# radio.net
KiCad netlist of a schematic drawn in Altium Designer
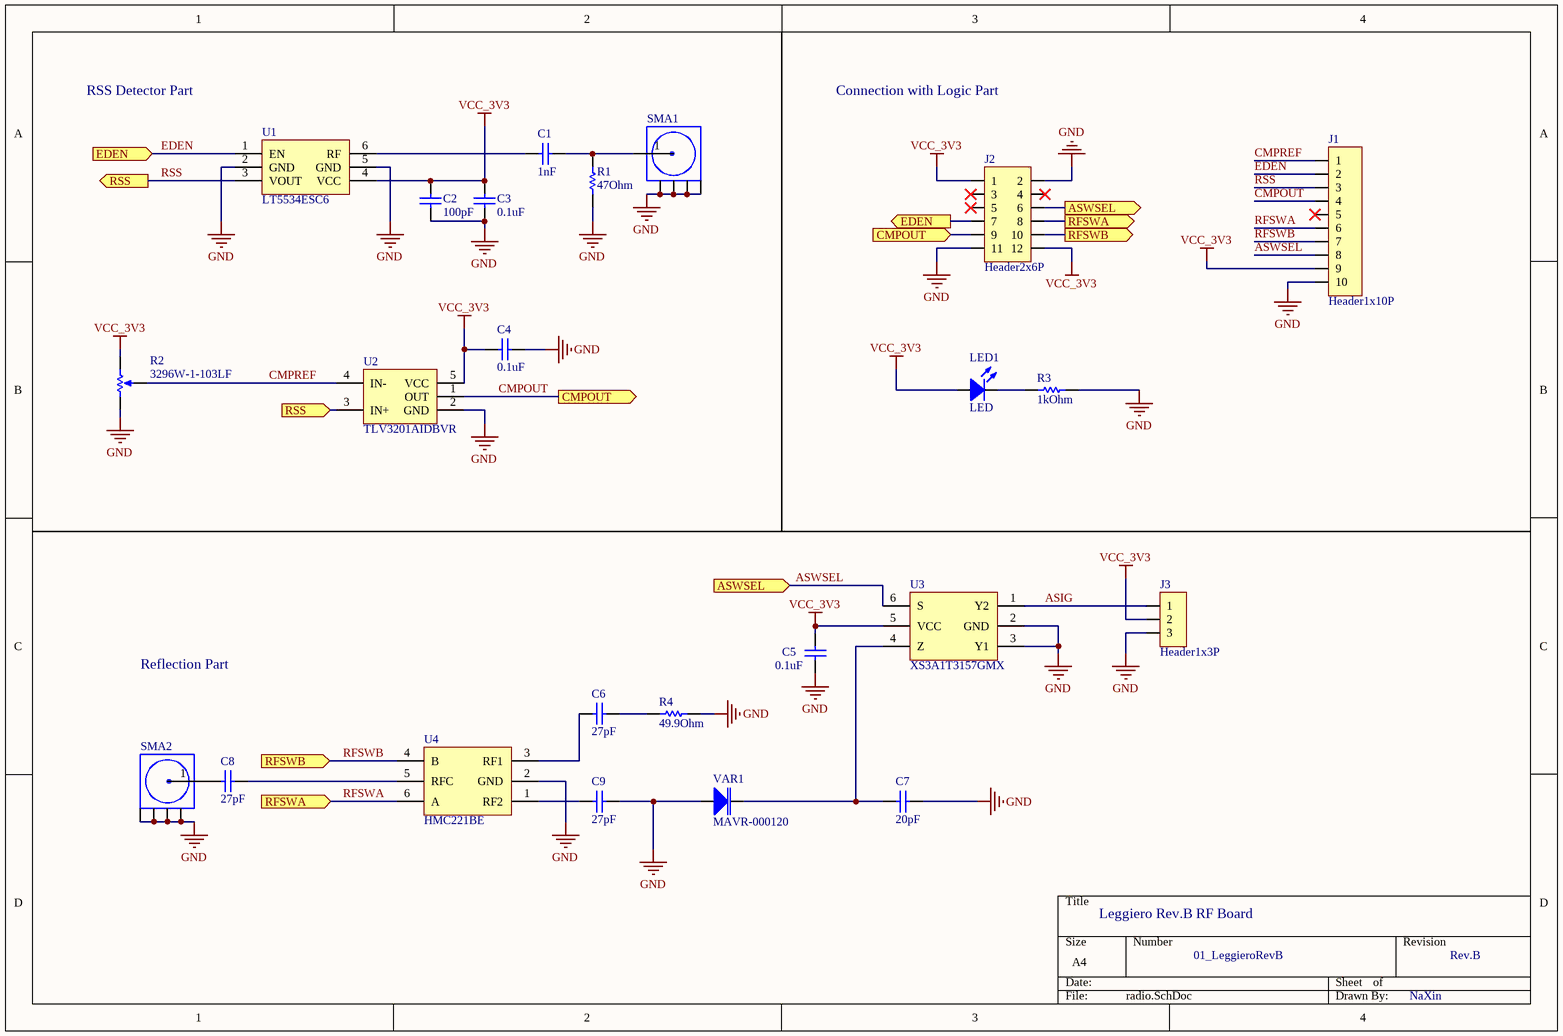
[diagram p0: radio.SchDoc]

(export (version "E")
  (design (tool "Eeschema 10.0.6"))
  (components
    (comp (ref "C1")
      (value "1nF")
      (footprint "C0402")
      (description "C597016")
      (libsource (lib "leggiero") (part "Cap"))
    )
    (comp (ref "C2") (value "100pF") (footprint "C0603") (libsource (lib "leggiero") (part "Cap")))
    (comp (ref "C3") (value "0.1uF") (footprint "C0402") (libsource (lib "leggiero") (part "Cap")))
    (comp (ref "C4") (value "0.1uF") (footprint "C0402") (libsource (lib "leggiero") (part "Cap")))
    (comp (ref "C5") (value "0.1uF") (footprint "C0402") (libsource (lib "leggiero") (part "Cap")))
    (comp (ref "C6")
      (value "27pF")
      (footprint "C0402")
      (description "C88883")
      (libsource (lib "leggiero") (part "Cap"))
    )
    (comp (ref "C7") (value "20pF") (footprint "C0402") (libsource (lib "leggiero") (part "Cap")))
    (comp (ref "C8")
      (value "27pF")
      (footprint "C0402")
      (description "C88883")
      (libsource (lib "leggiero") (part "Cap"))
    )
    (comp (ref "C9")
      (value "27pF")
      (footprint "C0402")
      (description "C88883")
      (libsource (lib "leggiero") (part "Cap"))
    )
    (comp (ref "J1")
      (value "Header1x10P")
      (footprint "Header1x10P")
      (description "C5156617")
      (libsource (lib "leggiero") (part "Header1x10P"))
    )
    (comp (ref "J2")
      (value "Header2x6P")
      (footprint "Header2x6P")
      (description "C92269")
      (libsource (lib "leggiero") (part "Header2x6P"))
    )
    (comp (ref "J3")
      (value "Header1x3P")
      (footprint "Header1x3P")
      (description "C7430359")
      (libsource (lib "leggiero") (part "Header1x3P"))
    )
    (comp (ref "LED1") (value "LED") (footprint "LED0603") (libsource (lib "leggiero") (part "LED")))
    (comp (ref "R1")
      (value "47Ohm")
      (footprint "R0402")
      (description "C491103")
      (libsource (lib "leggiero") (part "Res"))
    )
    (comp (ref "R2")
      (value "3296W-1-103LF")
      (footprint "3296W-1-103LF")
      (description "C34846")
      (libsource (lib "leggiero") (part "3296W-1-103LF"))
    )
    (comp (ref "R3") (value "1kOhm") (footprint "R0402") (libsource (lib "leggiero") (part "Res")))
    (comp (ref "R4")
      (value "49.9Ohm")
      (footprint "R0402")
      (description "C851030")
      (libsource (lib "leggiero") (part "Res"))
    )
    (comp (ref "SMA1")
      (value "RF2203017")
      (footprint "RF2203017")
      (description "C2982575")
      (libsource (lib "") (part "RF2203017_1"))
    )
    (comp (ref "SMA2")
      (value "RF2203017")
      (footprint "RF2203017")
      (description "C2982575")
      (libsource (lib "leggiero") (part "RF2203017"))
    )
    (comp (ref "U1")
      (value "LT5534ESC6")
      (footprint "LT5534ESC6#TRPBF")
      (description "C459867")
      (libsource (lib "leggiero") (part "LT5534ESC6"))
    )
    (comp (ref "U2")
      (value "TLV3201AIDBVR")
      (footprint "TLV3201AIDBVR")
      (description "C105188")
      (libsource (lib "leggiero") (part "TLV3201AIDBVR"))
    )
    (comp (ref "U3")
      (value "XS3A1T3157GMX")
      (footprint "XSON6_115")
      (description "C3657276")
      (libsource (lib "leggiero") (part "XS3A1T3157GMX"))
    )
    (comp (ref "U4")
      (value "HMC221BE")
      (footprint "SOT-23-6")
      (description "C1526247")
      (libsource (lib "leggiero") (part "HMC221BE"))
    )
    (comp (ref "VAR1")
      (value "MAVR-000120")
      (footprint "D0201")
      (description "C5139746")
      (libsource (lib "leggiero") (part "MAVR-000120"))
    )
  )
  (nets
    (net (code "1") (name "/ASIG") (class "Default")
      (node (ref "J3") (pin "1") (pinfunction "1_1") (pintype "passive"))
      (node (ref "U3") (pin "1") (pinfunction "Y2_1") (pintype "passive"))
    )
    (net (code "2") (name "/ASWSEL") (class "Default")
      (node (ref "J1") (pin "8") (pinfunction "8_8") (pintype "passive"))
      (node (ref "J2") (pin "6") (pinfunction "6_6") (pintype "passive"))
      (node (ref "U3") (pin "6") (pinfunction "S_6") (pintype "passive"))
    )
    (net (code "3") (name "/CMPOUT") (class "Default")
      (node (ref "J1") (pin "4") (pinfunction "4_4") (pintype "passive"))
      (node (ref "J2") (pin "9") (pinfunction "9_9") (pintype "passive"))
      (node (ref "U2") (pin "1") (pinfunction "OUT_1") (pintype "passive"))
    )
    (net (code "4") (name "/CMPREF") (class "Default")
      (node (ref "J1") (pin "1") (pinfunction "1_1") (pintype "passive"))
      (node (ref "R2") (pin "2") (pinfunction "WIPER_2") (pintype "passive"))
      (node (ref "U2") (pin "4") (pinfunction "IN-_4") (pintype "passive"))
    )
    (net (code "5") (name "/EDEN") (class "Default")
      (node (ref "J1") (pin "2") (pinfunction "2_2") (pintype "passive"))
      (node (ref "J2") (pin "7") (pinfunction "7_7") (pintype "passive"))
      (node (ref "U1") (pin "1") (pinfunction "EN_1") (pintype "passive"))
    )
    (net (code "6") (name "/RFSWA") (class "Default")
      (node (ref "J1") (pin "6") (pinfunction "6_6") (pintype "passive"))
      (node (ref "J2") (pin "8") (pinfunction "8_8") (pintype "passive"))
      (node (ref "U4") (pin "6") (pinfunction "A_6") (pintype "passive"))
    )
    (net (code "7") (name "/RFSWB") (class "Default")
      (node (ref "J1") (pin "7") (pinfunction "7_7") (pintype "passive"))
      (node (ref "J2") (pin "10") (pinfunction "10_10") (pintype "passive"))
      (node (ref "U4") (pin "4") (pinfunction "B_4") (pintype "passive"))
    )
    (net (code "8") (name "/RSS") (class "Default")
      (node (ref "J1") (pin "3") (pinfunction "3_3") (pintype "passive"))
      (node (ref "U1") (pin "3") (pinfunction "VOUT_3") (pintype "passive"))
      (node (ref "U2") (pin "3") (pinfunction "IN+_3") (pintype "passive"))
    )
    (net (code "9") (name "GND") (class "Default")
      (node (ref "C2") (pin "1") (pinfunction "1_1") (pintype "passive"))
      (node (ref "C3") (pin "1") (pinfunction "1_1") (pintype "passive"))
      (node (ref "C4") (pin "1") (pinfunction "1_1") (pintype "passive"))
      (node (ref "C5") (pin "2") (pinfunction "2_2") (pintype "passive"))
      (node (ref "C7") (pin "2") (pinfunction "2_2") (pintype "passive"))
      (node (ref "C9") (pin "2") (pinfunction "2_2") (pintype "passive"))
      (node (ref "J1") (pin "10") (pinfunction "10_10") (pintype "passive"))
      (node (ref "J2") (pin "11") (pinfunction "11_11") (pintype "passive"))
      (node (ref "J2") (pin "2") (pinfunction "2_2") (pintype "passive"))
      (node (ref "J3") (pin "3") (pinfunction "3_3") (pintype "passive"))
      (node (ref "R1") (pin "1") (pinfunction "1_1") (pintype "passive"))
      (node (ref "R2") (pin "3") (pinfunction "CW_3") (pintype "passive"))
      (node (ref "R3") (pin "1") (pinfunction "1_1") (pintype "passive"))
      (node (ref "R4") (pin "1") (pinfunction "1_1") (pintype "passive"))
      (node (ref "SMA1") (pin "2") (pinfunction "GND_2") (pintype "power_in"))
      (node (ref "SMA1") (pin "3") (pinfunction "GND_3") (pintype "power_in"))
      (node (ref "SMA1") (pin "4") (pinfunction "GND_4") (pintype "power_in"))
      (node (ref "SMA1") (pin "5") (pinfunction "GND_5") (pintype "power_in"))
      (node (ref "SMA2") (pin "2") (pinfunction "GND_2") (pintype "power_in"))
      (node (ref "SMA2") (pin "3") (pinfunction "GND_3") (pintype "power_in"))
      (node (ref "SMA2") (pin "4") (pinfunction "GND_4") (pintype "power_in"))
      (node (ref "SMA2") (pin "5") (pinfunction "GND_5") (pintype "power_in"))
      (node (ref "U1") (pin "2") (pinfunction "GND_2") (pintype "power_in"))
      (node (ref "U1") (pin "5") (pinfunction "GND_5") (pintype "power_in"))
      (node (ref "U2") (pin "2") (pinfunction "GND_2") (pintype "power_in"))
      (node (ref "U3") (pin "2") (pinfunction "GND_2") (pintype "power_in"))
      (node (ref "U3") (pin "3") (pinfunction "Y1_3") (pintype "passive"))
      (node (ref "U4") (pin "2") (pinfunction "GND_2") (pintype "power_in"))
      (node (ref "VAR1") (pin "2") (pinfunction "A_2") (pintype "passive"))
    )
    (net (code "10") (name "Net-(C6-Pad2)") (class "Default")
      (node (ref "C6") (pin "2") (pinfunction "2_2") (pintype "passive"))
      (node (ref "R4") (pin "2") (pinfunction "2_2") (pintype "passive"))
    )
    (net (code "11") (name "Net-(LED1-*-Pad2)") (class "Default")
      (node (ref "LED1") (pin "2") (pinfunction "*_2") (pintype "passive"))
      (node (ref "R3") (pin "2") (pinfunction "2_2") (pintype "passive"))
    )
    (net (code "12") (name "Net-(SMA1-SIG)") (class "Default")
      (node (ref "C1") (pin "2") (pinfunction "2_2") (pintype "passive"))
      (node (ref "R1") (pin "2") (pinfunction "2_2") (pintype "passive"))
      (node (ref "SMA1") (pin "1") (pinfunction "SIG_1") (pintype "passive"))
    )
    (net (code "13") (name "Net-(SMA2-SIG)") (class "Default")
      (node (ref "C8") (pin "1") (pinfunction "1_1") (pintype "passive"))
      (node (ref "SMA2") (pin "1") (pinfunction "SIG_1") (pintype "passive"))
    )
    (net (code "14") (name "Net-(U1-RF)") (class "Default")
      (node (ref "C1") (pin "1") (pinfunction "1_1") (pintype "passive"))
      (node (ref "U1") (pin "6") (pinfunction "RF_6") (pintype "passive"))
    )
    (net (code "15") (name "Net-(U3-Z)") (class "Default")
      (node (ref "C7") (pin "1") (pinfunction "1_1") (pintype "passive"))
      (node (ref "U3") (pin "4") (pinfunction "Z_4") (pintype "passive"))
      (node (ref "VAR1") (pin "1") (pinfunction "K_1") (pintype "passive"))
    )
    (net (code "16") (name "Net-(U4-RF1)") (class "Default")
      (node (ref "C6") (pin "1") (pinfunction "1_1") (pintype "passive"))
      (node (ref "U4") (pin "3") (pinfunction "RF1_3") (pintype "passive"))
    )
    (net (code "17") (name "Net-(U4-RF2)") (class "Default")
      (node (ref "C9") (pin "1") (pinfunction "1_1") (pintype "passive"))
      (node (ref "U4") (pin "1") (pinfunction "RF2_1") (pintype "passive"))
    )
    (net (code "18") (name "Net-(U4-RFC)") (class "Default")
      (node (ref "C8") (pin "2") (pinfunction "2_2") (pintype "passive"))
      (node (ref "U4") (pin "5") (pinfunction "RFC_5") (pintype "passive"))
    )
    (net (code "19") (name "VCC_3V3") (class "Default")
      (node (ref "C2") (pin "2") (pinfunction "2_2") (pintype "passive"))
      (node (ref "C3") (pin "2") (pinfunction "2_2") (pintype "passive"))
      (node (ref "C4") (pin "2") (pinfunction "2_2") (pintype "passive"))
      (node (ref "C5") (pin "1") (pinfunction "1_1") (pintype "passive"))
      (node (ref "J1") (pin "9") (pinfunction "9_9") (pintype "passive"))
      (node (ref "J2") (pin "1") (pinfunction "1_1") (pintype "passive"))
      (node (ref "J2") (pin "12") (pinfunction "12_12") (pintype "passive"))
      (node (ref "J3") (pin "2") (pinfunction "2_2") (pintype "passive"))
      (node (ref "LED1") (pin "1") (pinfunction "*_1") (pintype "passive"))
      (node (ref "R2") (pin "1") (pinfunction "CCW_1") (pintype "passive"))
      (node (ref "U1") (pin "4") (pinfunction "VCC_4") (pintype "power_in"))
      (node (ref "U2") (pin "5") (pinfunction "VCC_5") (pintype "power_in"))
      (node (ref "U3") (pin "5") (pinfunction "VCC_5") (pintype "power_in"))
    )
    (net (code "20") (name "unconnected-(J1-Pad5)") (class "Default")
      (node (ref "J1") (pin "5") (pinfunction "5_5") (pintype "passive+no_connect"))
    )
    (net (code "21") (name "unconnected-(J2-Pad3)") (class "Default")
      (node (ref "J2") (pin "3") (pinfunction "3_3") (pintype "passive+no_connect"))
    )
    (net (code "22") (name "unconnected-(J2-Pad4)") (class "Default")
      (node (ref "J2") (pin "4") (pinfunction "4_4") (pintype "passive+no_connect"))
    )
    (net (code "23") (name "unconnected-(J2-Pad5)") (class "Default")
      (node (ref "J2") (pin "5") (pinfunction "5_5") (pintype "passive+no_connect"))
    )
  )
)
